# nets_v2.net
KiCad netlist of a schematic drawn in EAGLE
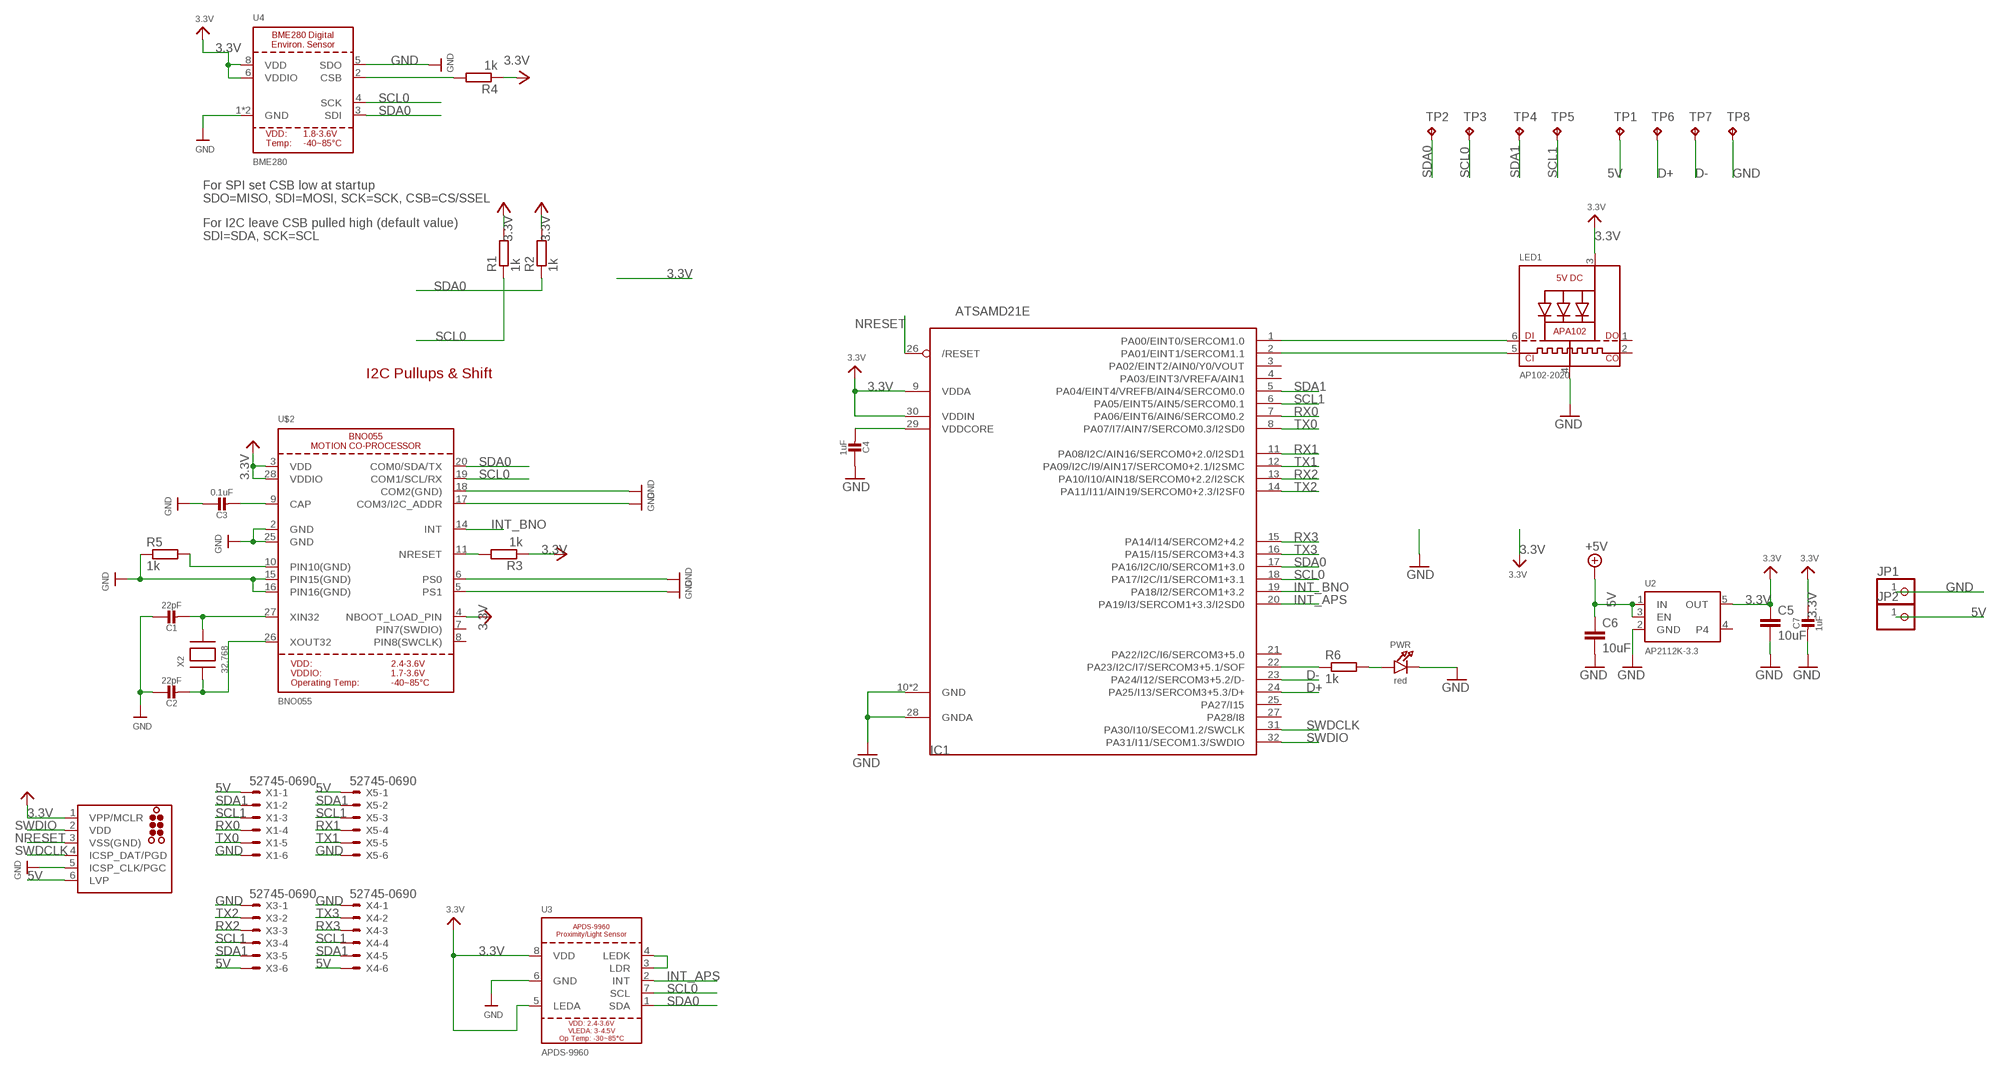
[diagram p0: schematic, sheet 1]

(export (version "E")
  (design (tool "Eeschema 10.0.6"))
  (components
    (comp (ref "C1")
      (value "22pF")
      (footprint "eagle-import:_0402NO")
      (fields (field (name "MF") "WURTH ELEKTRONIK") (field (name "MPN") "885012005042"))
      (libsource (lib "eagle-import") (part "CAP_CERAMIC_0402NO"))
    )
    (comp (ref "C2")
      (value "22pF")
      (footprint "eagle-import:_0402NO")
      (fields (field (name "MF") "WURTH ELEKTRONIK") (field (name "MPN") "885012005042"))
      (libsource (lib "eagle-import") (part "CAP_CERAMIC_0402NO"))
    )
    (comp (ref "C3")
      (value "0.1uF")
      (footprint "eagle-import:_0402NO")
      (fields (field (name "MF") "KEMET") (field (name "MPN") "R79IC3100Z340J"))
      (libsource (lib "eagle-import") (part "CAP_CERAMIC_0402NO"))
    )
    (comp (ref "C4")
      (value "1uF")
      (footprint "eagle-import:_0402NO")
      (libsource (lib "eagle-import") (part "CAP_CERAMIC_0402NO"))
    )
    (comp (ref "C5")
      (value "10uF")
      (footprint "eagle-import:C0603")
      (libsource (lib "eagle-import") (part "C-EUC0603"))
    )
    (comp (ref "C6")
      (value "10uF")
      (footprint "eagle-import:C0603")
      (libsource (lib "eagle-import") (part "C-EUC0603"))
    )
    (comp (ref "C7")
      (value "1uF")
      (footprint "eagle-import:_0402NO")
      (libsource (lib "eagle-import") (part "CAP_CERAMIC_0402NO"))
    )
    (comp (ref "IC1")
      (value "ATSAMD21E")
      (footprint "eagle-import:QFN32_5MM")
      (libsource (lib "eagle-import") (part "ATSAMD21E"))
    )
    (comp (ref "J1")
      (value "TC2030-ICSP-MCP-NL")
      (footprint "eagle-import:TC2030-MCP-NL")
      (libsource (lib "eagle-import") (part "TC2030-ICSP-MCP-NL"))
    )
    (comp (ref "JP1")
      (value "PINHD-1X1")
      (footprint "eagle-import:1X01")
      (libsource (lib "eagle-import") (part "PINHD-1X1"))
    )
    (comp (ref "JP2")
      (value "PINHD-1X1")
      (footprint "eagle-import:1X01")
      (libsource (lib "eagle-import") (part "PINHD-1X1"))
    )
    (comp (ref "LED1")
      (value "AP102-2020")
      (footprint "eagle-import:APA102_2020")
      (libsource (lib "eagle-import") (part "APA1022020"))
    )
    (comp (ref "PWR")
      (value "red")
      (footprint "eagle-import:CHIPLED_0603_NOOUTLINE")
      (libsource (lib "eagle-import") (part "LED0603_NOOUTLINE"))
    )
    (comp (ref "R1")
      (value "1k")
      (footprint "eagle-import:R0402")
      (libsource (lib "eagle-import") (part "R-EU_R0402"))
    )
    (comp (ref "R2")
      (value "1k")
      (footprint "eagle-import:R0402")
      (libsource (lib "eagle-import") (part "R-EU_R0402"))
    )
    (comp (ref "R3")
      (value "1k")
      (footprint "eagle-import:R0402")
      (libsource (lib "eagle-import") (part "R-EU_R0402"))
    )
    (comp (ref "R4")
      (value "1k")
      (footprint "eagle-import:R0402")
      (libsource (lib "eagle-import") (part "R-EU_R0402"))
    )
    (comp (ref "R5")
      (value "1k")
      (footprint "eagle-import:R0402")
      (libsource (lib "eagle-import") (part "R-EU_R0402"))
    )
    (comp (ref "R6")
      (value "1k")
      (footprint "eagle-import:R0402")
      (libsource (lib "eagle-import") (part "R-EU_R0402"))
    )
    (comp (ref "TP1")
      (value "TPTP10R")
      (footprint "eagle-import:TP10R")
      (libsource (lib "eagle-import") (part "TPTP10R"))
    )
    (comp (ref "TP2")
      (value "TPTP10R")
      (footprint "eagle-import:TP10R")
      (libsource (lib "eagle-import") (part "TPTP10R"))
    )
    (comp (ref "TP3")
      (value "TPTP10R")
      (footprint "eagle-import:TP10R")
      (libsource (lib "eagle-import") (part "TPTP10R"))
    )
    (comp (ref "TP4")
      (value "TPTP10R")
      (footprint "eagle-import:TP10R")
      (libsource (lib "eagle-import") (part "TPTP10R"))
    )
    (comp (ref "TP5")
      (value "TPTP10R")
      (footprint "eagle-import:TP10R")
      (libsource (lib "eagle-import") (part "TPTP10R"))
    )
    (comp (ref "TP6")
      (value "TPTP10R")
      (footprint "eagle-import:TP10R")
      (libsource (lib "eagle-import") (part "TPTP10R"))
    )
    (comp (ref "TP7")
      (value "TPTP10R")
      (footprint "eagle-import:TP10R")
      (libsource (lib "eagle-import") (part "TPTP10R"))
    )
    (comp (ref "TP8")
      (value "TPTP10R")
      (footprint "eagle-import:TP10R")
      (libsource (lib "eagle-import") (part "TPTP10R"))
    )
    (comp (ref "U$2")
      (value "BNO055")
      (footprint "eagle-import:BNO055")
      (libsource (lib "eagle-import") (part "BNO055"))
    )
    (comp (ref "U2")
      (value "AP2112K-3.3")
      (footprint "eagle-import:SOT23-5")
      (libsource (lib "eagle-import") (part "VREG_SOT23-5"))
    )
    (comp (ref "U3")
      (value "APDS-9960")
      (footprint "eagle-import:APDS-9960")
      (libsource (lib "eagle-import") (part "APDS-9960"))
    )
    (comp (ref "U4")
      (value "BME280")
      (footprint "eagle-import:BME280")
      (libsource (lib "eagle-import") (part "BME280"))
    )
    (comp (ref "X1")
      (value "52745-0690")
      (footprint "eagle-import:52745-0690")
      (fields (field (name "MF") "MOLEX") (field (name "OC_NEWARK") "unknown"))
      (libsource (lib "eagle-import") (part "52745-0690"))
    )
    (comp (ref "X2")
      (value "32.768")
      (footprint "eagle-import:XTAL3215")
      (libsource (lib "eagle-import") (part "XTAL-3.2X1.5"))
    )
    (comp (ref "X3")
      (value "52745-0690")
      (footprint "eagle-import:52745-0690")
      (fields (field (name "MF") "MOLEX") (field (name "OC_NEWARK") "unknown"))
      (libsource (lib "eagle-import") (part "52745-0690"))
    )
    (comp (ref "X4")
      (value "52745-0690")
      (footprint "eagle-import:52745-0690")
      (fields (field (name "MF") "MOLEX") (field (name "OC_NEWARK") "unknown"))
      (libsource (lib "eagle-import") (part "52745-0690"))
    )
    (comp (ref "X5")
      (value "52745-0690")
      (footprint "eagle-import:52745-0690")
      (fields (field (name "MF") "MOLEX") (field (name "OC_NEWARK") "unknown"))
      (libsource (lib "eagle-import") (part "52745-0690"))
    )
  )
  (nets
    (net (code "1") (name "+5V") (class "Default")
      (node (ref "C6") (pin "1") (pinfunction "1_1") (pintype "passive"))
      (node (ref "J1") (pin "6") (pinfunction "LVP_6") (pintype "bidirectional"))
      (node (ref "JP2") (pin "1") (pinfunction "1_1") (pintype "passive"))
      (node (ref "TP1") (pin "TP") (pinfunction "TP_TP") (pintype "input"))
      (node (ref "U2") (pin "1") (pinfunction "IN_1") (pintype "power_in"))
      (node (ref "U2") (pin "3") (pinfunction "EN_3") (pintype "input"))
      (node (ref "X1") (pin "1") (pinfunction "S_1") (pintype "passive"))
      (node (ref "X3") (pin "6") (pinfunction "S_6") (pintype "passive"))
      (node (ref "X4") (pin "6") (pinfunction "S_6") (pintype "passive"))
      (node (ref "X5") (pin "1") (pinfunction "S_1") (pintype "passive"))
    )
    (net (code "2") (name "/D+") (class "Default")
      (node (ref "IC1") (pin "24") (pinfunction "PA25/I13/SERCOM3+5.3/D+_24") (pintype "bidirectional"))
      (node (ref "TP6") (pin "TP") (pinfunction "TP_TP") (pintype "input"))
    )
    (net (code "3") (name "/D-") (class "Default")
      (node (ref "IC1") (pin "23") (pinfunction "PA24/I12/SERCOM3+5.2/D-_23") (pintype "bidirectional"))
      (node (ref "TP7") (pin "TP") (pinfunction "TP_TP") (pintype "input"))
    )
    (net (code "4") (name "/INT_APS") (class "Default")
      (node (ref "IC1") (pin "20") (pinfunction "PA19/I3/SERCOM1+3.3/I2SD0_20") (pintype "bidirectional"))
      (node (ref "U3") (pin "2") (pinfunction "INT_2") (pintype "output"))
    )
    (net (code "5") (name "/INT_BNO") (class "Default")
      (node (ref "IC1") (pin "19") (pinfunction "PA18/I2/SERCOM1+3.2_19") (pintype "bidirectional"))
      (node (ref "U$2") (pin "14") (pinfunction "INT_14") (pintype "output"))
    )
    (net (code "6") (name "/NRESET") (class "Default")
      (node (ref "IC1") (pin "26") (pinfunction "/RESET_26") (pintype "bidirectional"))
      (node (ref "J1") (pin "3") (pinfunction "VSS(GND)_3") (pintype "power_in"))
    )
    (net (code "7") (name "/RX0") (class "Default")
      (node (ref "IC1") (pin "7") (pinfunction "PA06/EINT6/AIN6/SERCOM0.2_7") (pintype "bidirectional"))
      (node (ref "X1") (pin "4") (pinfunction "S_4") (pintype "passive"))
    )
    (net (code "8") (name "/RX1") (class "Default")
      (node (ref "IC1") (pin "11") (pinfunction "PA08/I2C/AIN16/SERCOM0+2.0/I2SD1_11") (pintype "bidirectional"))
      (node (ref "X5") (pin "4") (pinfunction "S_4") (pintype "passive"))
    )
    (net (code "9") (name "/RX2") (class "Default")
      (node (ref "IC1") (pin "13") (pinfunction "PA10/I10/AIN18/SERCOM0+2.2/I2SCK_13") (pintype "bidirectional"))
      (node (ref "X3") (pin "3") (pinfunction "S_3") (pintype "passive"))
    )
    (net (code "10") (name "/RX3") (class "Default")
      (node (ref "IC1") (pin "15") (pinfunction "PA14/I14/SERCOM2+4.2_15") (pintype "bidirectional"))
      (node (ref "X4") (pin "3") (pinfunction "S_3") (pintype "passive"))
    )
    (net (code "11") (name "/SCL0") (class "Default")
      (node (ref "IC1") (pin "18") (pinfunction "PA17/I2C/I1/SERCOM1+3.1_18") (pintype "bidirectional"))
      (node (ref "R1") (pin "1") (pinfunction "1_1") (pintype "passive"))
      (node (ref "TP3") (pin "TP") (pinfunction "TP_TP") (pintype "input"))
      (node (ref "U$2") (pin "19") (pinfunction "COM1/SCL/RX_19") (pintype "bidirectional"))
      (node (ref "U3") (pin "7") (pinfunction "SCL_7") (pintype "input"))
      (node (ref "U4") (pin "4") (pinfunction "SCK_4") (pintype "input"))
    )
    (net (code "12") (name "/SCL1") (class "Default")
      (node (ref "IC1") (pin "6") (pinfunction "PA05/EINT5/AIN5/SERCOM0.1_6") (pintype "bidirectional"))
      (node (ref "TP5") (pin "TP") (pinfunction "TP_TP") (pintype "input"))
      (node (ref "X1") (pin "3") (pinfunction "S_3") (pintype "passive"))
      (node (ref "X3") (pin "4") (pinfunction "S_4") (pintype "passive"))
      (node (ref "X4") (pin "4") (pinfunction "S_4") (pintype "passive"))
      (node (ref "X5") (pin "3") (pinfunction "S_3") (pintype "passive"))
    )
    (net (code "13") (name "/SDA0") (class "Default")
      (node (ref "IC1") (pin "17") (pinfunction "PA16/I2C/I0/SERCOM1+3.0_17") (pintype "bidirectional"))
      (node (ref "R2") (pin "1") (pinfunction "1_1") (pintype "passive"))
      (node (ref "TP2") (pin "TP") (pinfunction "TP_TP") (pintype "input"))
      (node (ref "U$2") (pin "20") (pinfunction "COM0/SDA/TX_20") (pintype "bidirectional"))
      (node (ref "U3") (pin "1") (pinfunction "SDA_1") (pintype "bidirectional"))
      (node (ref "U4") (pin "3") (pinfunction "SDI_3") (pintype "input"))
    )
    (net (code "14") (name "/SDA1") (class "Default")
      (node (ref "IC1") (pin "5") (pinfunction "PA04/EINT4/VREFB/AIN4/SERCOM0.0_5") (pintype "bidirectional"))
      (node (ref "TP4") (pin "TP") (pinfunction "TP_TP") (pintype "input"))
      (node (ref "X1") (pin "2") (pinfunction "S_2") (pintype "passive"))
      (node (ref "X3") (pin "5") (pinfunction "S_5") (pintype "passive"))
      (node (ref "X4") (pin "5") (pinfunction "S_5") (pintype "passive"))
      (node (ref "X5") (pin "2") (pinfunction "S_2") (pintype "passive"))
    )
    (net (code "15") (name "/SWDCLK") (class "Default")
      (node (ref "IC1") (pin "31") (pinfunction "PA30/I10/SECOM1.2/SWCLK_31") (pintype "bidirectional"))
      (node (ref "J1") (pin "4") (pinfunction "ICSP_DAT/PGD_4") (pintype "bidirectional"))
    )
    (net (code "16") (name "/SWDIO") (class "Default")
      (node (ref "IC1") (pin "32") (pinfunction "PA31/I11/SECOM1.3/SWDIO_32") (pintype "bidirectional"))
      (node (ref "J1") (pin "2") (pinfunction "VDD_2") (pintype "power_in"))
    )
    (net (code "17") (name "/TX0") (class "Default")
      (node (ref "IC1") (pin "8") (pinfunction "PA07/I7/AIN7/SERCOM0.3/I2SD0_8") (pintype "bidirectional"))
      (node (ref "X1") (pin "5") (pinfunction "S_5") (pintype "passive"))
    )
    (net (code "18") (name "/TX1") (class "Default")
      (node (ref "IC1") (pin "12") (pinfunction "PA09/I2C/I9/AIN17/SERCOM0+2.1/I2SMC_12") (pintype "bidirectional"))
      (node (ref "X5") (pin "5") (pinfunction "S_5") (pintype "passive"))
    )
    (net (code "19") (name "/TX2") (class "Default")
      (node (ref "IC1") (pin "14") (pinfunction "PA11/I11/AIN19/SERCOM0+2.3/I2SF0_14") (pintype "bidirectional"))
      (node (ref "X3") (pin "2") (pinfunction "S_2") (pintype "passive"))
    )
    (net (code "20") (name "/TX3") (class "Default")
      (node (ref "IC1") (pin "16") (pinfunction "PA15/I15/SERCOM3+4.3_16") (pintype "bidirectional"))
      (node (ref "X4") (pin "2") (pinfunction "S_2") (pintype "passive"))
    )
    (net (code "21") (name "3.3V") (class "Default")
      (node (ref "C5") (pin "1") (pinfunction "1_1") (pintype "passive"))
      (node (ref "C7") (pin "1") (pinfunction "1_1") (pintype "passive"))
      (node (ref "IC1") (pin "30") (pinfunction "VDDIN_30") (pintype "power_in"))
      (node (ref "IC1") (pin "9") (pinfunction "VDDA_9") (pintype "power_in"))
      (node (ref "J1") (pin "1") (pinfunction "VPP/MCLR_1") (pintype "passive"))
      (node (ref "LED1") (pin "3") (pinfunction "VDD_3") (pintype "power_in"))
      (node (ref "R1") (pin "2") (pinfunction "2_2") (pintype "passive"))
      (node (ref "R2") (pin "2") (pinfunction "2_2") (pintype "passive"))
      (node (ref "R3") (pin "1") (pinfunction "1_1") (pintype "passive"))
      (node (ref "R4") (pin "1") (pinfunction "1_1") (pintype "passive"))
      (node (ref "U$2") (pin "28") (pinfunction "VDDIO_28") (pintype "power_in"))
      (node (ref "U$2") (pin "3") (pinfunction "VDD_3") (pintype "power_in"))
      (node (ref "U$2") (pin "4") (pinfunction "NBOOT_LOAD_PIN_4") (pintype "bidirectional"))
      (node (ref "U2") (pin "5") (pinfunction "OUT_5") (pintype "power_in"))
      (node (ref "U3") (pin "5") (pinfunction "LEDA_5") (pintype "power_in"))
      (node (ref "U3") (pin "8") (pinfunction "VDD_8") (pintype "power_in"))
      (node (ref "U4") (pin "6") (pinfunction "VDDIO_6") (pintype "power_in"))
      (node (ref "U4") (pin "8") (pinfunction "VDD_8") (pintype "power_in"))
    )
    (net (code "22") (name "GND") (class "Default")
      (node (ref "C1") (pin "1") (pinfunction "1_1") (pintype "passive"))
      (node (ref "C2") (pin "1") (pinfunction "1_1") (pintype "passive"))
      (node (ref "C3") (pin "1") (pinfunction "1_1") (pintype "passive"))
      (node (ref "C4") (pin "1") (pinfunction "1_1") (pintype "passive"))
      (node (ref "C5") (pin "2") (pinfunction "2_2") (pintype "passive"))
      (node (ref "C6") (pin "2") (pinfunction "2_2") (pintype "passive"))
      (node (ref "C7") (pin "2") (pinfunction "2_2") (pintype "passive"))
      (node (ref "IC1") (pin "10") (pinfunction "GND_10") (pintype "power_in"))
      (node (ref "IC1") (pin "28") (pinfunction "GNDA_28") (pintype "power_in"))
      (node (ref "IC1") (pin "33") (pinfunction "GND_33") (pintype "power_in"))
      (node (ref "J1") (pin "5") (pinfunction "ICSP_CLK/PGC_5") (pintype "output"))
      (node (ref "JP1") (pin "1") (pinfunction "1_1") (pintype "passive"))
      (node (ref "LED1") (pin "4") (pinfunction "GND_4") (pintype "power_in"))
      (node (ref "PWR") (pin "C") (pinfunction "C_C") (pintype "passive"))
      (node (ref "R5") (pin "1") (pinfunction "1_1") (pintype "passive"))
      (node (ref "TP8") (pin "TP") (pinfunction "TP_TP") (pintype "input"))
      (node (ref "U$2") (pin "15") (pinfunction "PIN15(GND)_15") (pintype "bidirectional"))
      (node (ref "U$2") (pin "16") (pinfunction "PIN16(GND)_16") (pintype "bidirectional"))
      (node (ref "U$2") (pin "17") (pinfunction "COM3/I2C_ADDR_17") (pintype "bidirectional"))
      (node (ref "U$2") (pin "18") (pinfunction "COM2(GND)_18") (pintype "bidirectional"))
      (node (ref "U$2") (pin "2") (pinfunction "GND_2") (pintype "power_in"))
      (node (ref "U$2") (pin "25") (pinfunction "GND_25") (pintype "power_in"))
      (node (ref "U$2") (pin "5") (pinfunction "PS1_5") (pintype "input"))
      (node (ref "U$2") (pin "6") (pinfunction "PS0_6") (pintype "input"))
      (node (ref "U2") (pin "2") (pinfunction "GND_2") (pintype "power_in"))
      (node (ref "U3") (pin "6") (pinfunction "GND_6") (pintype "power_in"))
      (node (ref "U4") (pin "1") (pinfunction "GND_1") (pintype "power_in"))
      (node (ref "U4") (pin "5") (pinfunction "SDO_5") (pintype "output"))
      (node (ref "U4") (pin "7") (pinfunction "GND_7") (pintype "power_in"))
      (node (ref "X1") (pin "6") (pinfunction "S_6") (pintype "passive"))
      (node (ref "X3") (pin "1") (pinfunction "S_1") (pintype "passive"))
      (node (ref "X4") (pin "1") (pinfunction "S_1") (pintype "passive"))
      (node (ref "X5") (pin "6") (pinfunction "S_6") (pintype "passive"))
    )
    (net (code "23") (name "Net-(IC1-PA00{slash}EINT0{slash}SERCOM1.0)") (class "Default")
      (node (ref "IC1") (pin "1") (pinfunction "PA00/EINT0/SERCOM1.0_1") (pintype "bidirectional"))
      (node (ref "LED1") (pin "6") (pinfunction "DI_6") (pintype "input"))
    )
    (net (code "24") (name "Net-(IC1-PA01{slash}EINT1{slash}SERCOM1.1)") (class "Default")
      (node (ref "IC1") (pin "2") (pinfunction "PA01/EINT1/SERCOM1.1_2") (pintype "bidirectional"))
      (node (ref "LED1") (pin "5") (pinfunction "CKI_5") (pintype "input"))
    )
    (net (code "25") (name "Net-(IC1-PA23{slash}I2C{slash}I7{slash}SERCOM3+5.1{slash}SOF)") (class "Default")
      (node (ref "IC1") (pin "22") (pinfunction "PA23/I2C/I7/SERCOM3+5.1/SOF_22") (pintype "bidirectional"))
      (node (ref "R6") (pin "1") (pinfunction "1_1") (pintype "passive"))
    )
    (net (code "26") (name "Net-(IC1-VDDCORE)") (class "Default")
      (node (ref "C4") (pin "2") (pinfunction "2_2") (pintype "passive"))
      (node (ref "IC1") (pin "29") (pinfunction "VDDCORE_29") (pintype "power_in"))
    )
    (net (code "27") (name "Net-(PWR-PadA)") (class "Default")
      (node (ref "PWR") (pin "A") (pinfunction "A_A") (pintype "passive"))
      (node (ref "R6") (pin "2") (pinfunction "2_2") (pintype "passive"))
    )
    (net (code "28") (name "Net-(U$2-CAP)") (class "Default")
      (node (ref "C3") (pin "2") (pinfunction "2_2") (pintype "passive"))
      (node (ref "U$2") (pin "9") (pinfunction "CAP_9") (pintype "passive"))
    )
    (net (code "29") (name "Net-(U$2-NRESET)") (class "Default")
      (node (ref "R3") (pin "2") (pinfunction "2_2") (pintype "passive"))
      (node (ref "U$2") (pin "11") (pinfunction "NRESET_11") (pintype "bidirectional"))
    )
    (net (code "30") (name "Net-(U$2-PIN10(GND))") (class "Default")
      (node (ref "R5") (pin "2") (pinfunction "2_2") (pintype "passive"))
      (node (ref "U$2") (pin "10") (pinfunction "PIN10(GND)_10") (pintype "bidirectional"))
    )
    (net (code "31") (name "Net-(U$2-XIN32)") (class "Default")
      (node (ref "C1") (pin "2") (pinfunction "2_2") (pintype "passive"))
      (node (ref "U$2") (pin "27") (pinfunction "XIN32_27") (pintype "input"))
      (node (ref "X2") (pin "P$2") (pinfunction "P$2_P$2") (pintype "bidirectional"))
    )
    (net (code "32") (name "Net-(U$2-XOUT32)") (class "Default")
      (node (ref "C2") (pin "2") (pinfunction "2_2") (pintype "passive"))
      (node (ref "U$2") (pin "26") (pinfunction "XOUT32_26") (pintype "output"))
      (node (ref "X2") (pin "P$1") (pinfunction "P$1_P$1") (pintype "bidirectional"))
    )
    (net (code "33") (name "Net-(U3-LDR)") (class "Default")
      (node (ref "U3") (pin "3") (pinfunction "LDR_3") (pintype "bidirectional"))
      (node (ref "U3") (pin "4") (pinfunction "LEDK_4") (pintype "bidirectional"))
    )
    (net (code "34") (name "Net-(U4-CSB)") (class "Default")
      (node (ref "R4") (pin "2") (pinfunction "2_2") (pintype "passive"))
      (node (ref "U4") (pin "2") (pinfunction "CSB_2") (pintype "input"))
    )
    (net (code "35") (name "unconnected-(IC1-PA02{slash}EINT2{slash}AIN0{slash}Y0{slash}VOUT-Pad3)") (class "Default")
      (node (ref "IC1") (pin "3") (pinfunction "PA02/EINT2/AIN0/Y0/VOUT_3") (pintype "bidirectional"))
    )
    (net (code "36") (name "unconnected-(IC1-PA03{slash}EINT3{slash}VREFA{slash}AIN1-Pad4)") (class "Default")
      (node (ref "IC1") (pin "4") (pinfunction "PA03/EINT3/VREFA/AIN1_4") (pintype "bidirectional"))
    )
    (net (code "37") (name "unconnected-(IC1-PA22{slash}I2C{slash}I6{slash}SERCOM3+5.0-Pad21)") (class "Default")
      (node (ref "IC1") (pin "21") (pinfunction "PA22/I2C/I6/SERCOM3+5.0_21") (pintype "bidirectional"))
    )
    (net (code "38") (name "unconnected-(IC1-PA27{slash}I15-Pad25)") (class "Default")
      (node (ref "IC1") (pin "25") (pinfunction "PA27/I15_25") (pintype "bidirectional"))
    )
    (net (code "39") (name "unconnected-(IC1-PA28{slash}I8-Pad27)") (class "Default")
      (node (ref "IC1") (pin "27") (pinfunction "PA28/I8_27") (pintype "bidirectional"))
    )
    (net (code "40") (name "unconnected-(LED1-CKO-Pad2)") (class "Default")
      (node (ref "LED1") (pin "2") (pinfunction "CKO_2") (pintype "output"))
    )
    (net (code "41") (name "unconnected-(LED1-DO-Pad1)") (class "Default")
      (node (ref "LED1") (pin "1") (pinfunction "DO_1") (pintype "output"))
    )
    (net (code "42") (name "unconnected-(U$2-PIN7(SWDIO)-Pad7)") (class "Default")
      (node (ref "U$2") (pin "7") (pinfunction "PIN7(SWDIO)_7") (pintype "bidirectional"))
    )
    (net (code "43") (name "unconnected-(U$2-PIN8(SWCLK)-Pad8)") (class "Default")
      (node (ref "U$2") (pin "8") (pinfunction "PIN8(SWCLK)_8") (pintype "bidirectional"))
    )
    (net (code "44") (name "unconnected-(U2-P4-Pad4)") (class "Default")
      (node (ref "U2") (pin "4") (pinfunction "P4_4") (pintype "bidirectional"))
    )
  )
)
